# RF_filter.net
KiCad netlist of a schematic drawn in Altium Designer
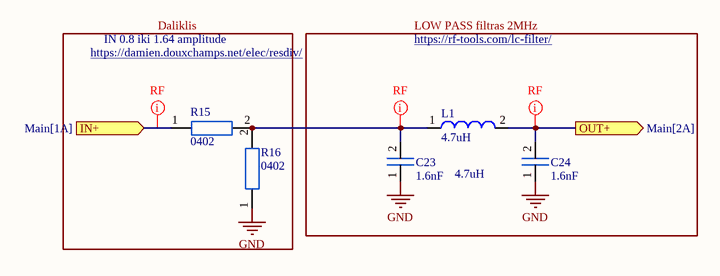
[diagram p0: RF_filter.SchDoc]

(export (version "E")
  (design (tool "Eeschema 10.0.6"))
  (components
    (comp (ref "C23")
      (value "1.6nF")
      (footprint "0402_footprint")
      (description "0402 capacitor")
      (libsource (lib "Schlib1") (part "Capacitor_0402"))
    )
    (comp (ref "C24")
      (value "1.6nF")
      (footprint "0402_footprint")
      (description "0402 capacitor")
      (libsource (lib "Schlib1") (part "Capacitor_0402"))
    )
    (comp (ref "L1")
      (value "4.7uH")
      (footprint "0603_FOOTPRINT")
      (description "0603 inductor")
      (libsource (lib "Schlib1") (part "Inductor_0603"))
    )
    (comp (ref "R15")
      (value "0402")
      (footprint "0402_footprint")
      (libsource (lib "Schlib1") (part "Resistor_0402"))
    )
    (comp (ref "R16")
      (value "0402")
      (footprint "0402_footprint")
      (libsource (lib "Schlib1") (part "Resistor_0402"))
    )
  )
  (nets
    (net (code "1") (name "/IN+") (class "Default")
      (node (ref "R15") (pin "1") (pinfunction "1_1") (pintype "passive"))
    )
    (net (code "2") (name "/OUT+") (class "Default")
      (node (ref "C24") (pin "2") (pinfunction "2_2") (pintype "passive"))
      (node (ref "L1") (pin "2") (pinfunction "2_2") (pintype "passive"))
    )
    (net (code "3") (name "GND") (class "Default")
      (node (ref "C23") (pin "1") (pinfunction "1_1") (pintype "passive"))
      (node (ref "C24") (pin "1") (pinfunction "1_1") (pintype "passive"))
      (node (ref "R16") (pin "1") (pinfunction "1_1") (pintype "passive"))
    )
    (net (code "4") (name "Net-(C23-Pad2)") (class "Default")
      (node (ref "C23") (pin "2") (pinfunction "2_2") (pintype "passive"))
      (node (ref "L1") (pin "1") (pinfunction "1_1") (pintype "passive"))
      (node (ref "R15") (pin "2") (pinfunction "2_2") (pintype "passive"))
      (node (ref "R16") (pin "2") (pinfunction "2_2") (pintype "passive"))
    )
  )
)
